# mubi-ESP32-30.net
KiCad netlist of a schematic drawn in EAGLE
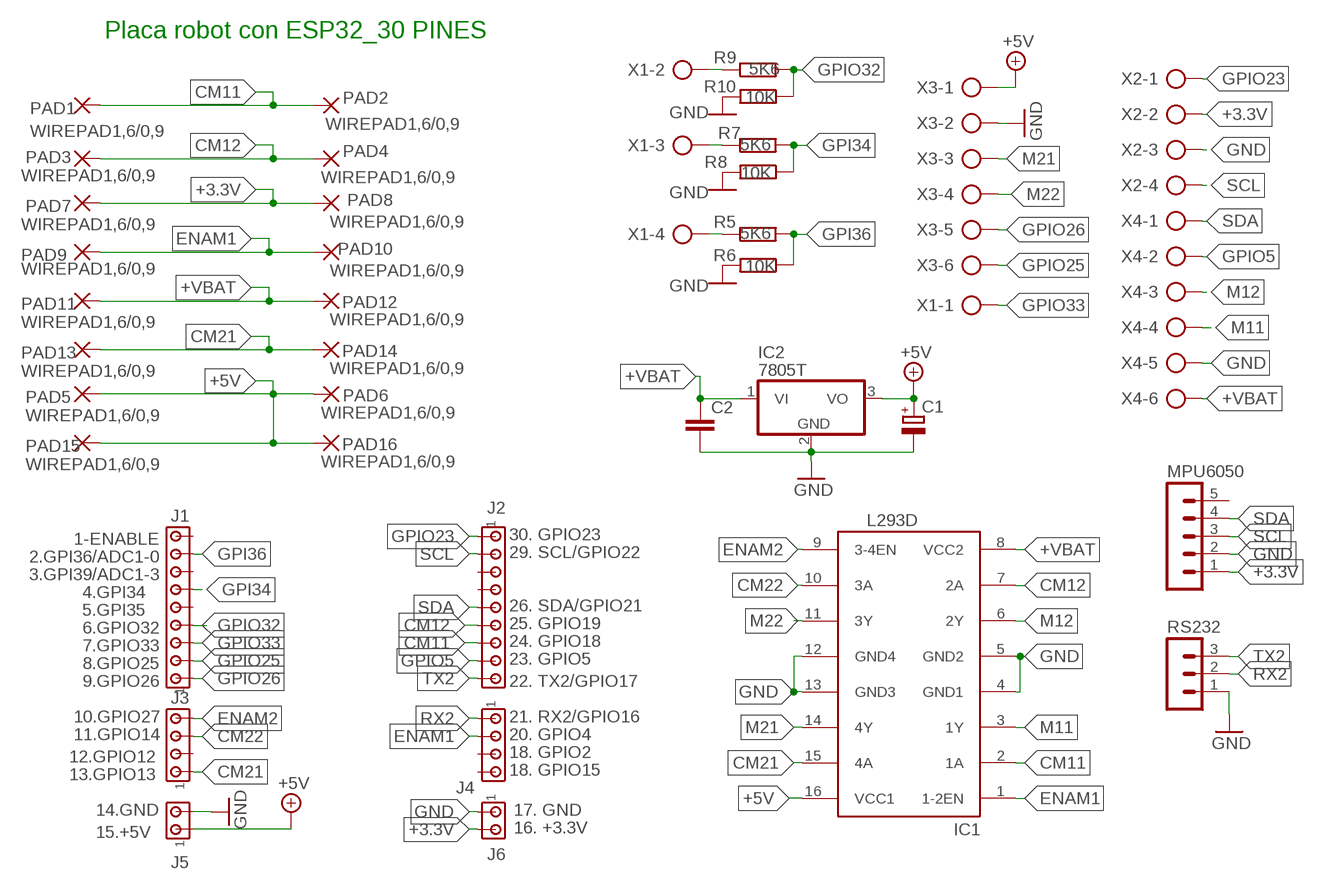
[diagram p0: schematic, sheet 1]

(export (version "E")
  (design (tool "Eeschema 10.0.6"))
  (components
    (comp (ref "C1")
      (value "CPOL-EUE2.5-6")
      (footprint "eagle-import:E2,5-6")
      (libsource (lib "eagle-import") (part "CPOL-EUE2.5-6"))
    )
    (comp (ref "C2")
      (value "C-EU025-025X050")
      (footprint "eagle-import:C025-025X050")
      (libsource (lib "eagle-import") (part "C-EU025-025X050"))
    )
    (comp (ref "IC1")
      (value "L293D")
      (footprint "eagle-import:DIL16")
      (libsource (lib "eagle-import") (part "L293D"))
    )
    (comp (ref "IC2")
      (value "7805T")
      (footprint "eagle-import:TO220H")
      (libsource (lib "eagle-import") (part "78T05"))
    )
    (comp (ref "J1")
      (value "MTA09-100")
      (footprint "eagle-import:10X09MTA")
      (libsource (lib "eagle-import") (part "MTA09-100"))
    )
    (comp (ref "J2")
      (value "MTA09-100")
      (footprint "eagle-import:10X09MTA")
      (libsource (lib "eagle-import") (part "MTA09-100"))
    )
    (comp (ref "J3")
      (value "MTA04-100")
      (footprint "eagle-import:10X04MTA")
      (libsource (lib "eagle-import") (part "MTA04-100"))
    )
    (comp (ref "J4")
      (value "MTA04-100")
      (footprint "eagle-import:10X04MTA")
      (libsource (lib "eagle-import") (part "MTA04-100"))
    )
    (comp (ref "J5")
      (value "MTA02-100")
      (footprint "eagle-import:10X02MTA")
      (libsource (lib "eagle-import") (part "MTA02-100"))
    )
    (comp (ref "J6")
      (value "MTA02-100")
      (footprint "eagle-import:10X02MTA")
      (libsource (lib "eagle-import") (part "MTA02-100"))
    )
    (comp (ref "MPU6050")
      (value "MA05-1")
      (footprint "eagle-import:MA05-1")
      (libsource (lib "eagle-import") (part "MA05-1"))
    )
    (comp (ref "PAD1")
      (value "WIREPAD1,6/0,9")
      (footprint "eagle-import:1,6_0,9")
      (libsource (lib "eagle-import") (part "WIREPAD1,6/0,9"))
    )
    (comp (ref "PAD2")
      (value "WIREPAD1,6/0,9")
      (footprint "eagle-import:1,6_0,9")
      (libsource (lib "eagle-import") (part "WIREPAD1,6/0,9"))
    )
    (comp (ref "PAD3")
      (value "WIREPAD1,6/0,9")
      (footprint "eagle-import:1,6_0,9")
      (libsource (lib "eagle-import") (part "WIREPAD1,6/0,9"))
    )
    (comp (ref "PAD4")
      (value "WIREPAD1,6/0,9")
      (footprint "eagle-import:1,6_0,9")
      (libsource (lib "eagle-import") (part "WIREPAD1,6/0,9"))
    )
    (comp (ref "PAD5")
      (value "WIREPAD1,6/0,9")
      (footprint "eagle-import:1,6_0,9")
      (libsource (lib "eagle-import") (part "WIREPAD1,6/0,9"))
    )
    (comp (ref "PAD6")
      (value "WIREPAD1,6/0,9")
      (footprint "eagle-import:1,6_0,9")
      (libsource (lib "eagle-import") (part "WIREPAD1,6/0,9"))
    )
    (comp (ref "PAD7")
      (value "WIREPAD1,6/0,9")
      (footprint "eagle-import:1,6_0,9")
      (libsource (lib "eagle-import") (part "WIREPAD1,6/0,9"))
    )
    (comp (ref "PAD8")
      (value "WIREPAD1,6/0,9")
      (footprint "eagle-import:1,6_0,9")
      (libsource (lib "eagle-import") (part "WIREPAD1,6/0,9"))
    )
    (comp (ref "PAD9")
      (value "WIREPAD1,6/0,9")
      (footprint "eagle-import:1,6_0,9")
      (libsource (lib "eagle-import") (part "WIREPAD1,6/0,9"))
    )
    (comp (ref "PAD10")
      (value "WIREPAD1,6/0,9")
      (footprint "eagle-import:1,6_0,9")
      (libsource (lib "eagle-import") (part "WIREPAD1,6/0,9"))
    )
    (comp (ref "PAD11")
      (value "WIREPAD1,6/0,9")
      (footprint "eagle-import:1,6_0,9")
      (libsource (lib "eagle-import") (part "WIREPAD1,6/0,9"))
    )
    (comp (ref "PAD12")
      (value "WIREPAD1,6/0,9")
      (footprint "eagle-import:1,6_0,9")
      (libsource (lib "eagle-import") (part "WIREPAD1,6/0,9"))
    )
    (comp (ref "PAD13")
      (value "WIREPAD1,6/0,9")
      (footprint "eagle-import:1,6_0,9")
      (libsource (lib "eagle-import") (part "WIREPAD1,6/0,9"))
    )
    (comp (ref "PAD14")
      (value "WIREPAD1,6/0,9")
      (footprint "eagle-import:1,6_0,9")
      (libsource (lib "eagle-import") (part "WIREPAD1,6/0,9"))
    )
    (comp (ref "PAD15")
      (value "WIREPAD1,6/0,9")
      (footprint "eagle-import:1,6_0,9")
      (libsource (lib "eagle-import") (part "WIREPAD1,6/0,9"))
    )
    (comp (ref "PAD16")
      (value "WIREPAD1,6/0,9")
      (footprint "eagle-import:1,6_0,9")
      (libsource (lib "eagle-import") (part "WIREPAD1,6/0,9"))
    )
    (comp (ref "R5")
      (value "5K6")
      (footprint "eagle-import:0204_5")
      (libsource (lib "eagle-import") (part "R-EU_0204/5"))
    )
    (comp (ref "R6")
      (value "10K")
      (footprint "eagle-import:0204_5")
      (libsource (lib "eagle-import") (part "R-EU_0204/5"))
    )
    (comp (ref "R7")
      (value "5K6")
      (footprint "eagle-import:0204_5")
      (libsource (lib "eagle-import") (part "R-EU_0204/5"))
    )
    (comp (ref "R8")
      (value "10K")
      (footprint "eagle-import:0204_5")
      (libsource (lib "eagle-import") (part "R-EU_0204/5"))
    )
    (comp (ref "R9")
      (value "5K6")
      (footprint "eagle-import:0204_5")
      (libsource (lib "eagle-import") (part "R-EU_0204/5"))
    )
    (comp (ref "R10")
      (value "10K")
      (footprint "eagle-import:0204_5")
      (libsource (lib "eagle-import") (part "R-EU_0204/5"))
    )
    (comp (ref "RS232")
      (value "MA03-1")
      (footprint "eagle-import:MA03-1")
      (libsource (lib "eagle-import") (part "MA03-1"))
    )
    (comp (ref "X1")
      (value "AK500/4-H")
      (footprint "eagle-import:AK500_4-H")
      (libsource (lib "eagle-import") (part "AK500/4-H"))
    )
    (comp (ref "X2")
      (value "AK500/4-H")
      (footprint "eagle-import:AK500_4-H")
      (libsource (lib "eagle-import") (part "AK500/4-H"))
    )
    (comp (ref "X3")
      (value "AK500/6-H")
      (footprint "eagle-import:AK500_6-H")
      (libsource (lib "eagle-import") (part "AK500/6-H"))
    )
    (comp (ref "X4")
      (value "AK500/6-H")
      (footprint "eagle-import:AK500_6-H")
      (libsource (lib "eagle-import") (part "AK500/6-H"))
    )
  )
  (nets
    (net (code "1") (name "+3.3V") (class "Default")
      (node (ref "J6") (pin "2") (pinfunction "2_2") (pintype "passive"))
      (node (ref "MPU6050") (pin "1") (pinfunction "1_1") (pintype "passive"))
      (node (ref "PAD7") (pin "1") (pinfunction "P_1") (pintype "passive"))
      (node (ref "PAD8") (pin "1") (pinfunction "P_1") (pintype "passive"))
      (node (ref "X2") (pin "2") (pinfunction "KL_2") (pintype "passive"))
    )
    (net (code "2") (name "+5V") (class "Default")
      (node (ref "C1") (pin "+") (pinfunction "+_+") (pintype "passive"))
      (node (ref "IC1") (pin "16") (pinfunction "VCC1_16") (pintype "power_in"))
      (node (ref "IC2") (pin "3") (pinfunction "VO_3") (pintype "passive"))
      (node (ref "J5") (pin "1") (pinfunction "1_1") (pintype "passive"))
      (node (ref "PAD15") (pin "1") (pinfunction "P_1") (pintype "passive"))
      (node (ref "PAD16") (pin "1") (pinfunction "P_1") (pintype "passive"))
      (node (ref "PAD5") (pin "1") (pinfunction "P_1") (pintype "passive"))
      (node (ref "PAD6") (pin "1") (pinfunction "P_1") (pintype "passive"))
      (node (ref "X3") (pin "1") (pinfunction "KL_1") (pintype "passive"))
    )
    (net (code "3") (name "+VBAT") (class "Default")
      (node (ref "C2") (pin "1") (pinfunction "1_1") (pintype "passive"))
      (node (ref "IC1") (pin "8") (pinfunction "VCC2_8") (pintype "power_in"))
      (node (ref "IC2") (pin "1") (pinfunction "VI_1") (pintype "input"))
      (node (ref "PAD11") (pin "1") (pinfunction "P_1") (pintype "passive"))
      (node (ref "PAD12") (pin "1") (pinfunction "P_1") (pintype "passive"))
      (node (ref "X4") (pin "6") (pinfunction "KL_6") (pintype "passive"))
    )
    (net (code "4") (name "CM11") (class "Default")
      (node (ref "IC1") (pin "2") (pinfunction "1A_2") (pintype "input"))
      (node (ref "J2") (pin "7") (pinfunction "7_7") (pintype "passive"))
      (node (ref "PAD1") (pin "1") (pinfunction "P_1") (pintype "passive"))
      (node (ref "PAD2") (pin "1") (pinfunction "P_1") (pintype "passive"))
    )
    (net (code "5") (name "CM12") (class "Default")
      (node (ref "IC1") (pin "7") (pinfunction "2A_7") (pintype "input"))
      (node (ref "J2") (pin "6") (pinfunction "6_6") (pintype "passive"))
      (node (ref "PAD3") (pin "1") (pinfunction "P_1") (pintype "passive"))
      (node (ref "PAD4") (pin "1") (pinfunction "P_1") (pintype "passive"))
    )
    (net (code "6") (name "CM21") (class "Default")
      (node (ref "IC1") (pin "15") (pinfunction "4A_15") (pintype "input"))
      (node (ref "J3") (pin "1") (pinfunction "1_1") (pintype "passive"))
      (node (ref "PAD13") (pin "1") (pinfunction "P_1") (pintype "passive"))
      (node (ref "PAD14") (pin "1") (pinfunction "P_1") (pintype "passive"))
    )
    (net (code "7") (name "CM22") (class "Default")
      (node (ref "IC1") (pin "10") (pinfunction "3A_10") (pintype "input"))
      (node (ref "J3") (pin "3") (pinfunction "3_3") (pintype "passive"))
    )
    (net (code "8") (name "ENAM1") (class "Default")
      (node (ref "IC1") (pin "1") (pinfunction "1-2EN_1") (pintype "input"))
      (node (ref "J4") (pin "2") (pinfunction "2_2") (pintype "passive"))
      (node (ref "PAD10") (pin "1") (pinfunction "P_1") (pintype "passive"))
      (node (ref "PAD9") (pin "1") (pinfunction "P_1") (pintype "passive"))
    )
    (net (code "9") (name "ENAM2") (class "Default")
      (node (ref "IC1") (pin "9") (pinfunction "3-4EN_9") (pintype "input"))
      (node (ref "J3") (pin "4") (pinfunction "4_4") (pintype "passive"))
    )
    (net (code "10") (name "GND") (class "Default")
      (node (ref "C1") (pin "-") (pinfunction "-_-") (pintype "passive"))
      (node (ref "C2") (pin "2") (pinfunction "2_2") (pintype "passive"))
      (node (ref "IC1") (pin "12") (pinfunction "GND4_12") (pintype "power_in"))
      (node (ref "IC1") (pin "13") (pinfunction "GND3_13") (pintype "power_in"))
      (node (ref "IC1") (pin "4") (pinfunction "GND1_4") (pintype "power_in"))
      (node (ref "IC1") (pin "5") (pinfunction "GND2_5") (pintype "power_in"))
      (node (ref "IC2") (pin "2") (pinfunction "GND_2") (pintype "passive"))
      (node (ref "J5") (pin "2") (pinfunction "2_2") (pintype "passive"))
      (node (ref "J6") (pin "1") (pinfunction "1_1") (pintype "passive"))
      (node (ref "MPU6050") (pin "2") (pinfunction "2_2") (pintype "passive"))
      (node (ref "R10") (pin "2") (pinfunction "2_2") (pintype "passive"))
      (node (ref "R6") (pin "2") (pinfunction "2_2") (pintype "passive"))
      (node (ref "R8") (pin "2") (pinfunction "2_2") (pintype "passive"))
      (node (ref "RS232") (pin "1") (pinfunction "1_1") (pintype "passive"))
      (node (ref "X2") (pin "3") (pinfunction "KL_3") (pintype "passive"))
      (node (ref "X3") (pin "2") (pinfunction "KL_2") (pintype "passive"))
      (node (ref "X4") (pin "5") (pinfunction "KL_5") (pintype "passive"))
    )
    (net (code "11") (name "GPI34") (class "Default")
      (node (ref "J1") (pin "6") (pinfunction "6_6") (pintype "passive"))
      (node (ref "R7") (pin "2") (pinfunction "2_2") (pintype "passive"))
      (node (ref "R8") (pin "1") (pinfunction "1_1") (pintype "passive"))
    )
    (net (code "12") (name "GPI36") (class "Default")
      (node (ref "J1") (pin "8") (pinfunction "8_8") (pintype "passive"))
      (node (ref "R5") (pin "2") (pinfunction "2_2") (pintype "passive"))
      (node (ref "R6") (pin "1") (pinfunction "1_1") (pintype "passive"))
    )
    (net (code "13") (name "GPIO5") (class "Default")
      (node (ref "J2") (pin "8") (pinfunction "8_8") (pintype "passive"))
      (node (ref "X4") (pin "2") (pinfunction "KL_2") (pintype "passive"))
    )
    (net (code "14") (name "GPIO23") (class "Default")
      (node (ref "J2") (pin "1") (pinfunction "1_1") (pintype "passive"))
      (node (ref "X2") (pin "1") (pinfunction "KL_1") (pintype "passive"))
    )
    (net (code "15") (name "GPIO25") (class "Default")
      (node (ref "J1") (pin "2") (pinfunction "2_2") (pintype "passive"))
      (node (ref "X3") (pin "6") (pinfunction "KL_6") (pintype "passive"))
    )
    (net (code "16") (name "GPIO26") (class "Default")
      (node (ref "J1") (pin "1") (pinfunction "1_1") (pintype "passive"))
      (node (ref "X3") (pin "5") (pinfunction "KL_5") (pintype "passive"))
    )
    (net (code "17") (name "GPIO32") (class "Default")
      (node (ref "J1") (pin "4") (pinfunction "4_4") (pintype "passive"))
      (node (ref "R10") (pin "1") (pinfunction "1_1") (pintype "passive"))
      (node (ref "R9") (pin "2") (pinfunction "2_2") (pintype "passive"))
    )
    (net (code "18") (name "GPIO33") (class "Default")
      (node (ref "J1") (pin "3") (pinfunction "3_3") (pintype "passive"))
      (node (ref "X1") (pin "1") (pinfunction "KL_1") (pintype "passive"))
    )
    (net (code "19") (name "M11") (class "Default")
      (node (ref "IC1") (pin "3") (pinfunction "1Y_3") (pintype "output"))
      (node (ref "X4") (pin "4") (pinfunction "KL_4") (pintype "passive"))
    )
    (net (code "20") (name "M12") (class "Default")
      (node (ref "IC1") (pin "6") (pinfunction "2Y_6") (pintype "output"))
      (node (ref "X4") (pin "3") (pinfunction "KL_3") (pintype "passive"))
    )
    (net (code "21") (name "M21") (class "Default")
      (node (ref "IC1") (pin "14") (pinfunction "4Y_14") (pintype "output"))
      (node (ref "X3") (pin "3") (pinfunction "KL_3") (pintype "passive"))
    )
    (net (code "22") (name "M22") (class "Default")
      (node (ref "IC1") (pin "11") (pinfunction "3Y_11") (pintype "output"))
      (node (ref "X3") (pin "4") (pinfunction "KL_4") (pintype "passive"))
    )
    (net (code "23") (name "Net-(X1B-KL)") (class "Default")
      (node (ref "R9") (pin "1") (pinfunction "1_1") (pintype "passive"))
      (node (ref "X1") (pin "2") (pinfunction "KL_2") (pintype "passive"))
    )
    (net (code "24") (name "Net-(X1C-KL)") (class "Default")
      (node (ref "R7") (pin "1") (pinfunction "1_1") (pintype "passive"))
      (node (ref "X1") (pin "3") (pinfunction "KL_3") (pintype "passive"))
    )
    (net (code "25") (name "Net-(X1D-KL)") (class "Default")
      (node (ref "R5") (pin "1") (pinfunction "1_1") (pintype "passive"))
      (node (ref "X1") (pin "4") (pinfunction "KL_4") (pintype "passive"))
    )
    (net (code "26") (name "RX2") (class "Default")
      (node (ref "J4") (pin "1") (pinfunction "1_1") (pintype "passive"))
      (node (ref "RS232") (pin "2") (pinfunction "2_2") (pintype "passive"))
    )
    (net (code "27") (name "SCL") (class "Default")
      (node (ref "J2") (pin "2") (pinfunction "2_2") (pintype "passive"))
      (node (ref "MPU6050") (pin "3") (pinfunction "3_3") (pintype "passive"))
      (node (ref "X2") (pin "4") (pinfunction "KL_4") (pintype "passive"))
    )
    (net (code "28") (name "SDA") (class "Default")
      (node (ref "J2") (pin "5") (pinfunction "5_5") (pintype "passive"))
      (node (ref "MPU6050") (pin "4") (pinfunction "4_4") (pintype "passive"))
      (node (ref "X4") (pin "1") (pinfunction "KL_1") (pintype "passive"))
    )
    (net (code "29") (name "TX2") (class "Default")
      (node (ref "J2") (pin "9") (pinfunction "9_9") (pintype "passive"))
      (node (ref "RS232") (pin "3") (pinfunction "3_3") (pintype "passive"))
    )
    (net (code "30") (name "unconnected-(J1-Pad5)") (class "Default")
      (node (ref "J1") (pin "5") (pinfunction "5_5") (pintype "passive"))
    )
    (net (code "31") (name "unconnected-(J1-Pad7)") (class "Default")
      (node (ref "J1") (pin "7") (pinfunction "7_7") (pintype "passive"))
    )
    (net (code "32") (name "unconnected-(J1-Pad9)") (class "Default")
      (node (ref "J1") (pin "9") (pinfunction "9_9") (pintype "passive"))
    )
    (net (code "33") (name "unconnected-(J2-Pad3)") (class "Default")
      (node (ref "J2") (pin "3") (pinfunction "3_3") (pintype "passive"))
    )
    (net (code "34") (name "unconnected-(J2-Pad4)") (class "Default")
      (node (ref "J2") (pin "4") (pinfunction "4_4") (pintype "passive"))
    )
    (net (code "35") (name "unconnected-(J3-Pad2)") (class "Default")
      (node (ref "J3") (pin "2") (pinfunction "2_2") (pintype "passive"))
    )
    (net (code "36") (name "unconnected-(J4-Pad3)") (class "Default")
      (node (ref "J4") (pin "3") (pinfunction "3_3") (pintype "passive"))
    )
    (net (code "37") (name "unconnected-(J4-Pad4)") (class "Default")
      (node (ref "J4") (pin "4") (pinfunction "4_4") (pintype "passive"))
    )
    (net (code "38") (name "unconnected-(MPU6050-Pad5)") (class "Default")
      (node (ref "MPU6050") (pin "5") (pinfunction "5_5") (pintype "passive"))
    )
  )
)
